# FONA-Data-Logger-Board.net
KiCad netlist of a schematic drawn in EAGLE
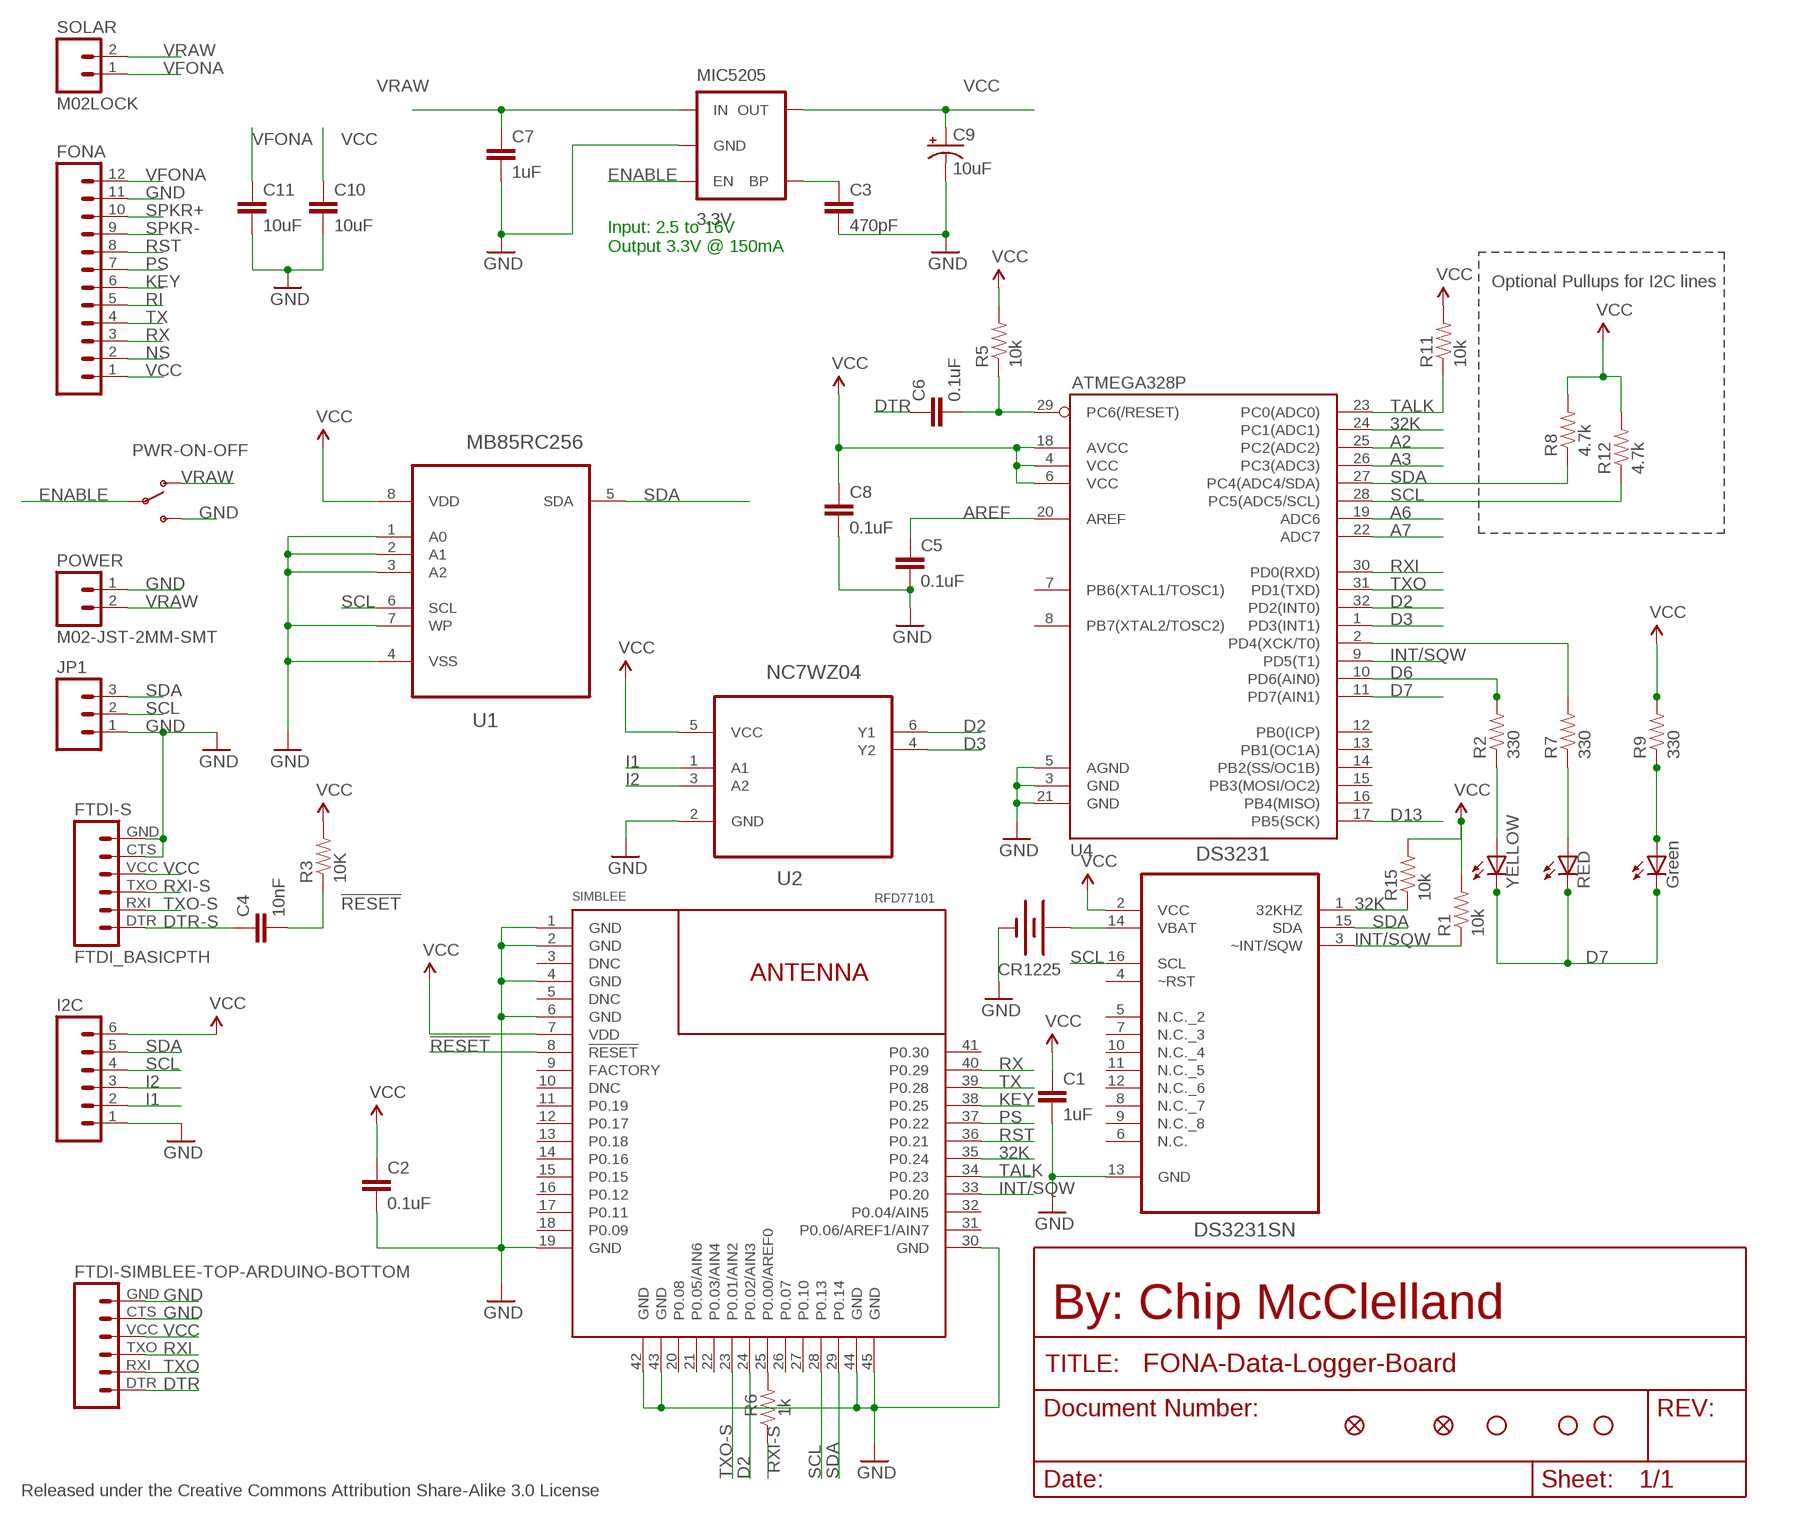
[diagram p0: schematic, sheet 1]

(export (version "E")
  (design (tool "Eeschema 10.0.6"))
  (components
    (comp (ref "ATMEGA328P")
      (value "U4")
      (footprint "eagle-import:TQFP32-08")
      (libsource (lib "eagle-import") (part "ATMEGA168"))
    )
    (comp (ref "C1")
      (value "1uF")
      (footprint "eagle-import:0805")
      (libsource (lib "eagle-import") (part "CAP0805"))
    )
    (comp (ref "C2")
      (value "0.1uF")
      (footprint "eagle-import:0805")
      (libsource (lib "eagle-import") (part "CAP0805"))
    )
    (comp (ref "C3")
      (value "470pF")
      (footprint "eagle-import:0805")
      (libsource (lib "eagle-import") (part "SparkFun-Passives_CAP0805"))
    )
    (comp (ref "C4")
      (value "10nF")
      (footprint "eagle-import:0805")
      (libsource (lib "eagle-import") (part "SparkFun-Passives_CAP0805"))
    )
    (comp (ref "C5")
      (value "0.1uF")
      (footprint "eagle-import:0805")
      (libsource (lib "eagle-import") (part "CAP0805"))
    )
    (comp (ref "C6")
      (value "0.1uF")
      (footprint "eagle-import:0805")
      (libsource (lib "eagle-import") (part "CAP0805"))
    )
    (comp (ref "C7")
      (value "1uF")
      (footprint "eagle-import:0805")
      (libsource (lib "eagle-import") (part "SparkFun-Passives_CAP0805"))
    )
    (comp (ref "C8")
      (value "0.1uF")
      (footprint "eagle-import:0805")
      (libsource (lib "eagle-import") (part "CAP0805"))
    )
    (comp (ref "C9")
      (value "10uF")
      (footprint "eagle-import:EIA3216")
      (libsource (lib "eagle-import") (part "CAP_POL1206"))
    )
    (comp (ref "C10")
      (value "10uF")
      (footprint "eagle-import:0805")
      (libsource (lib "eagle-import") (part "CAP0805"))
    )
    (comp (ref "C11")
      (value "10uF")
      (footprint "eagle-import:0805")
      (libsource (lib "eagle-import") (part "CAP0805"))
    )
    (comp (ref "CR1225")
      (value "BATTERY12MM")
      (footprint "eagle-import:BATTCON_12MM")
      (libsource (lib "eagle-import") (part "BATTERY12MM"))
    )
    (comp (ref "DS3231")
      (value "DS3231SN")
      (footprint "eagle-import:SOIC127P1032X265-16N")
      (fields (field (name "MPN") "DS3231SN#"))
      (libsource (lib "eagle-import") (part "DS3231SN"))
    )
    (comp (ref "FID1")
      (value "FIDUCIALUFIDUCIAL")
      (footprint "eagle-import:MICRO-FIDUCIAL")
      (libsource (lib "eagle-import") (part "FIDUCIALUFIDUCIAL"))
    )
    (comp (ref "FID2")
      (value "FIDUCIALUFIDUCIAL")
      (footprint "eagle-import:MICRO-FIDUCIAL")
      (libsource (lib "eagle-import") (part "FIDUCIALUFIDUCIAL"))
    )
    (comp (ref "FONA")
      (value "M12PTH")
      (footprint "eagle-import:1X12")
      (libsource (lib "eagle-import") (part "M12PTH"))
    )
    (comp (ref "FTDI-S")
      (value "FTDI_BASICPTH")
      (footprint "eagle-import:FTDI_BASIC")
      (libsource (lib "eagle-import") (part "FTDI_BASICPTH"))
    )
    (comp (ref "FTDI-SIMBLEE-TOP-ARDUINO-BOTTOM")
      (value "FTDI Basic")
      (footprint "eagle-import:FTDI_BASIC")
      (libsource (lib "eagle-import") (part "FTDI_BASICPTH"))
    )
    (comp (ref "G")
      (value "Green")
      (footprint "eagle-import:CHIPLED_0805")
      (libsource (lib "eagle-import") (part "LEDCHIPLED_0805"))
    )
    (comp (ref "I2C")
      (value "M06LOCK")
      (footprint "eagle-import:1X06_LOCK")
      (libsource (lib "eagle-import") (part "M06LOCK"))
    )
    (comp (ref "JP1")
      (value "M03LOCK")
      (footprint "eagle-import:1X03_LOCK")
      (libsource (lib "eagle-import") (part "M03LOCK"))
    )
    (comp (ref "JP3")
      (value "STAND-OFF")
      (footprint "eagle-import:STAND-OFF")
      (libsource (lib "eagle-import") (part "STAND-OFF"))
    )
    (comp (ref "JP4")
      (value "STAND-OFF")
      (footprint "eagle-import:STAND-OFF")
      (libsource (lib "eagle-import") (part "STAND-OFF"))
    )
    (comp (ref "JP6")
      (value "STAND-OFF")
      (footprint "eagle-import:STAND-OFF")
      (libsource (lib "eagle-import") (part "STAND-OFF"))
    )
    (comp (ref "MB85RC256")
      (value "U1")
      (footprint "eagle-import:SOIC127P600X175-8N")
      (fields (field (name "MPN") "MB85RC128PNF-G-JNE1"))
      (libsource (lib "eagle-import") (part "MB85RC128PNF-G-JNE1"))
    )
    (comp (ref "MIC5205")
      (value "3.3V")
      (footprint "eagle-import:SOT23-5")
      (libsource (lib "eagle-import") (part "MIC52053.3V"))
    )
    (comp (ref "NC7WZ04")
      (value "U2")
      (footprint "eagle-import:SOT65P210X110-6N")
      (fields (field (name "MPN") "NC7WZ04P6X"))
      (libsource (lib "eagle-import") (part "NC7WZ04P6X"))
    )
    (comp (ref "POWER")
      (value "M02-JST-2MM-SMT")
      (footprint "eagle-import:JST-2-SMD")
      (libsource (lib "eagle-import") (part "M02-JST-2MM-SMT"))
    )
    (comp (ref "PWR-ON-OFF")
      (value "SWITCH-SPDTPTH")
      (footprint "eagle-import:SWITCH-SPDT")
      (libsource (lib "eagle-import") (part "SWITCH-SPDTPTH"))
    )
    (comp (ref "R")
      (value "RED")
      (footprint "eagle-import:CHIPLED_0805")
      (libsource (lib "eagle-import") (part "LEDCHIPLED_0805"))
    )
    (comp (ref "R1")
      (value "10k")
      (footprint "eagle-import:0805")
      (libsource (lib "eagle-import") (part "RESISTOR0805-RES"))
    )
    (comp (ref "R2")
      (value "330")
      (footprint "eagle-import:0603-RES")
      (libsource (lib "eagle-import") (part "RESISTOR0603"))
    )
    (comp (ref "R3")
      (value "10K")
      (footprint "eagle-import:0805")
      (libsource (lib "eagle-import") (part "RESISTOR0805-RES"))
    )
    (comp (ref "R5")
      (value "10k")
      (footprint "eagle-import:0805")
      (libsource (lib "eagle-import") (part "RESISTOR0805-RES"))
    )
    (comp (ref "R6")
      (value "1k")
      (footprint "eagle-import:0805")
      (libsource (lib "eagle-import") (part "RESISTOR0805-RES"))
    )
    (comp (ref "R7")
      (value "330")
      (footprint "eagle-import:0603-RES")
      (libsource (lib "eagle-import") (part "RESISTOR0603"))
    )
    (comp (ref "R8")
      (value "4.7k")
      (footprint "eagle-import:0805")
      (libsource (lib "eagle-import") (part "SparkFun-Resistors_RESISTOR0805-RES"))
    )
    (comp (ref "R9")
      (value "330")
      (footprint "eagle-import:0603-RES")
      (libsource (lib "eagle-import") (part "RESISTOR0603"))
    )
    (comp (ref "R11")
      (value "10k")
      (footprint "eagle-import:0805")
      (libsource (lib "eagle-import") (part "RESISTOR0805-RES"))
    )
    (comp (ref "R12")
      (value "4.7k")
      (footprint "eagle-import:0805")
      (libsource (lib "eagle-import") (part "SparkFun-Resistors_RESISTOR0805-RES"))
    )
    (comp (ref "R15")
      (value "10k")
      (footprint "eagle-import:0805")
      (libsource (lib "eagle-import") (part "RESISTOR0805-RES"))
    )
    (comp (ref "SIMBLEE")
      (value "RFD77101")
      (footprint "eagle-import:RFD77101")
      (libsource (lib "eagle-import") (part "RFD77101"))
    )
    (comp (ref "SOLAR")
      (value "M02LOCK")
      (footprint "eagle-import:1X02_LOCK")
      (libsource (lib "eagle-import") (part "M02LOCK"))
    )
    (comp (ref "Y")
      (value "YELLOW")
      (footprint "eagle-import:CHIPLED_0805")
      (libsource (lib "eagle-import") (part "LEDCHIPLED_0805"))
    )
  )
  (nets
    (net (code "1") (name "/32K") (class "Default")
      (node (ref "ATMEGA328P") (pin "24") (pinfunction "PC1(ADC1)_24") (pintype "bidirectional"))
      (node (ref "DS3231") (pin "1") (pinfunction "32KHZ_1") (pintype "output"))
      (node (ref "R15") (pin "1") (pinfunction "1_1") (pintype "passive"))
      (node (ref "SIMBLEE") (pin "35") (pinfunction "P0.24_35") (pintype "bidirectional"))
    )
    (net (code "2") (name "/A2") (class "Default")
      (node (ref "ATMEGA328P") (pin "25") (pinfunction "PC2(ADC2)_25") (pintype "bidirectional"))
    )
    (net (code "3") (name "/A3") (class "Default")
      (node (ref "ATMEGA328P") (pin "26") (pinfunction "PC3(ADC3)_26") (pintype "bidirectional"))
    )
    (net (code "4") (name "/A6") (class "Default")
      (node (ref "ATMEGA328P") (pin "19") (pinfunction "ADC6_19") (pintype "bidirectional"))
    )
    (net (code "5") (name "/A7") (class "Default")
      (node (ref "ATMEGA328P") (pin "22") (pinfunction "ADC7_22") (pintype "bidirectional"))
    )
    (net (code "6") (name "/AREF") (class "Default")
      (node (ref "ATMEGA328P") (pin "20") (pinfunction "AREF_20") (pintype "bidirectional"))
      (node (ref "C5") (pin "1") (pinfunction "1_1") (pintype "passive"))
    )
    (net (code "7") (name "/D2") (class "Default")
      (node (ref "ATMEGA328P") (pin "32") (pinfunction "PD2(INT0)_32") (pintype "bidirectional"))
      (node (ref "NC7WZ04") (pin "6") (pinfunction "Y1_6") (pintype "output"))
      (node (ref "SIMBLEE") (pin "24") (pinfunction "P0.02/AIN3_24") (pintype "bidirectional"))
    )
    (net (code "8") (name "/D3") (class "Default")
      (node (ref "ATMEGA328P") (pin "1") (pinfunction "PD3(INT1)_1") (pintype "bidirectional"))
      (node (ref "NC7WZ04") (pin "4") (pinfunction "Y2_4") (pintype "output"))
    )
    (net (code "9") (name "/D6") (class "Default")
      (node (ref "ATMEGA328P") (pin "10") (pinfunction "PD6(AIN0)_10") (pintype "bidirectional"))
      (node (ref "R2") (pin "2") (pinfunction "2_2") (pintype "passive"))
    )
    (net (code "10") (name "/D7") (class "Default")
      (node (ref "ATMEGA328P") (pin "11") (pinfunction "PD7(AIN1)_11") (pintype "bidirectional"))
      (node (ref "G") (pin "C") (pinfunction "C_C") (pintype "passive"))
      (node (ref "R") (pin "C") (pinfunction "C_C") (pintype "passive"))
      (node (ref "Y") (pin "C") (pinfunction "C_C") (pintype "passive"))
    )
    (net (code "11") (name "/D13") (class "Default")
      (node (ref "ATMEGA328P") (pin "17") (pinfunction "PB5(SCK)_17") (pintype "bidirectional"))
    )
    (net (code "12") (name "/DTR") (class "Default")
      (node (ref "C6") (pin "1") (pinfunction "1_1") (pintype "passive"))
      (node (ref "FTDI-SIMBLEE-TOP-ARDUINO-BOTTOM") (pin "DTR") (pinfunction "1_DTR") (pintype "passive"))
    )
    (net (code "13") (name "/DTR-S") (class "Default")
      (node (ref "C4") (pin "1") (pinfunction "1_1") (pintype "passive"))
      (node (ref "FTDI-S") (pin "DTR") (pinfunction "1_DTR") (pintype "passive"))
    )
    (net (code "14") (name "/ENABLE") (class "Default")
      (node (ref "MIC5205") (pin "3") (pinfunction "EN_3") (pintype "input"))
      (node (ref "PWR-ON-OFF") (pin "2") (pinfunction "P_2") (pintype "passive"))
    )
    (net (code "15") (name "/I1") (class "Default")
      (node (ref "I2C") (pin "2") (pinfunction "2_2") (pintype "passive"))
      (node (ref "NC7WZ04") (pin "1") (pinfunction "A1_1") (pintype "input"))
    )
    (net (code "16") (name "/I2") (class "Default")
      (node (ref "I2C") (pin "3") (pinfunction "3_3") (pintype "passive"))
      (node (ref "NC7WZ04") (pin "3") (pinfunction "A2_3") (pintype "input"))
    )
    (net (code "17") (name "/INT{slash}SQW") (class "Default")
      (node (ref "ATMEGA328P") (pin "9") (pinfunction "PD5(T1)_9") (pintype "bidirectional"))
      (node (ref "DS3231") (pin "3") (pinfunction "~{INT/SQW}_3") (pintype "output"))
      (node (ref "R1") (pin "1") (pinfunction "1_1") (pintype "passive"))
      (node (ref "SIMBLEE") (pin "33") (pinfunction "P0.20_33") (pintype "bidirectional"))
    )
    (net (code "18") (name "/KEY") (class "Default")
      (node (ref "FONA") (pin "6") (pinfunction "6_6") (pintype "passive"))
      (node (ref "SIMBLEE") (pin "38") (pinfunction "P0.25_38") (pintype "bidirectional"))
    )
    (net (code "19") (name "/NS") (class "Default")
      (node (ref "FONA") (pin "2") (pinfunction "2_2") (pintype "passive"))
    )
    (net (code "20") (name "/PS") (class "Default")
      (node (ref "FONA") (pin "7") (pinfunction "7_7") (pintype "passive"))
      (node (ref "SIMBLEE") (pin "37") (pinfunction "P0.22_37") (pintype "bidirectional"))
    )
    (net (code "21") (name "/RI") (class "Default")
      (node (ref "FONA") (pin "5") (pinfunction "5_5") (pintype "passive"))
    )
    (net (code "22") (name "/RST") (class "Default")
      (node (ref "FONA") (pin "8") (pinfunction "8_8") (pintype "passive"))
      (node (ref "SIMBLEE") (pin "36") (pinfunction "P0.21_36") (pintype "bidirectional"))
    )
    (net (code "23") (name "/RX") (class "Default")
      (node (ref "FONA") (pin "3") (pinfunction "3_3") (pintype "passive"))
      (node (ref "SIMBLEE") (pin "40") (pinfunction "P0.29_40") (pintype "bidirectional"))
    )
    (net (code "24") (name "/RXI") (class "Default")
      (node (ref "ATMEGA328P") (pin "30") (pinfunction "PD0(RXD)_30") (pintype "bidirectional"))
      (node (ref "FTDI-SIMBLEE-TOP-ARDUINO-BOTTOM") (pin "TXO") (pinfunction "3_TXO") (pintype "passive"))
    )
    (net (code "25") (name "/RXI-S") (class "Default")
      (node (ref "FTDI-S") (pin "TXO") (pinfunction "3_TXO") (pintype "passive"))
      (node (ref "R6") (pin "1") (pinfunction "1_1") (pintype "passive"))
    )
    (net (code "26") (name "/SCL") (class "Default")
      (node (ref "ATMEGA328P") (pin "28") (pinfunction "PC5(ADC5/SCL)_28") (pintype "bidirectional"))
      (node (ref "DS3231") (pin "16") (pinfunction "SCL_16") (pintype "input"))
      (node (ref "I2C") (pin "4") (pinfunction "4_4") (pintype "passive"))
      (node (ref "JP1") (pin "2") (pinfunction "2_2") (pintype "passive"))
      (node (ref "MB85RC256") (pin "6") (pinfunction "SCL_6") (pintype "input"))
      (node (ref "R12") (pin "1") (pinfunction "1_1") (pintype "passive"))
      (node (ref "SIMBLEE") (pin "28") (pinfunction "P0.13_28") (pintype "bidirectional"))
    )
    (net (code "27") (name "/SDA") (class "Default")
      (node (ref "ATMEGA328P") (pin "27") (pinfunction "PC4(ADC4/SDA)_27") (pintype "bidirectional"))
      (node (ref "DS3231") (pin "15") (pinfunction "SDA_15") (pintype "bidirectional"))
      (node (ref "I2C") (pin "5") (pinfunction "5_5") (pintype "passive"))
      (node (ref "JP1") (pin "3") (pinfunction "3_3") (pintype "passive"))
      (node (ref "MB85RC256") (pin "5") (pinfunction "SDA_5") (pintype "bidirectional"))
      (node (ref "R8") (pin "1") (pinfunction "1_1") (pintype "passive"))
      (node (ref "SIMBLEE") (pin "29") (pinfunction "P0.14_29") (pintype "bidirectional"))
    )
    (net (code "28") (name "/SPKR+") (class "Default")
      (node (ref "FONA") (pin "10") (pinfunction "10_10") (pintype "passive"))
    )
    (net (code "29") (name "/SPKR-") (class "Default")
      (node (ref "FONA") (pin "9") (pinfunction "9_9") (pintype "passive"))
    )
    (net (code "30") (name "/TALK") (class "Default")
      (node (ref "ATMEGA328P") (pin "23") (pinfunction "PC0(ADC0)_23") (pintype "bidirectional"))
      (node (ref "R11") (pin "1") (pinfunction "1_1") (pintype "passive"))
      (node (ref "SIMBLEE") (pin "34") (pinfunction "P0.23_34") (pintype "bidirectional"))
    )
    (net (code "31") (name "/TX") (class "Default")
      (node (ref "FONA") (pin "4") (pinfunction "4_4") (pintype "passive"))
      (node (ref "SIMBLEE") (pin "39") (pinfunction "P0.28_39") (pintype "bidirectional"))
    )
    (net (code "32") (name "/TXO") (class "Default")
      (node (ref "ATMEGA328P") (pin "31") (pinfunction "PD1(TXD)_31") (pintype "bidirectional"))
      (node (ref "FTDI-SIMBLEE-TOP-ARDUINO-BOTTOM") (pin "RXI") (pinfunction "2_RXI") (pintype "passive"))
    )
    (net (code "33") (name "/TXO-S") (class "Default")
      (node (ref "FTDI-S") (pin "RXI") (pinfunction "2_RXI") (pintype "passive"))
      (node (ref "SIMBLEE") (pin "23") (pinfunction "P0.01/AIN2_23") (pintype "bidirectional"))
    )
    (net (code "34") (name "/VFONA") (class "Default")
      (node (ref "C11") (pin "1") (pinfunction "1_1") (pintype "passive"))
      (node (ref "FONA") (pin "12") (pinfunction "12_12") (pintype "passive"))
      (node (ref "SOLAR") (pin "1") (pinfunction "1_1") (pintype "passive"))
    )
    (net (code "35") (name "/VRAW") (class "Default")
      (node (ref "C7") (pin "1") (pinfunction "1_1") (pintype "passive"))
      (node (ref "MIC5205") (pin "1") (pinfunction "IN_1") (pintype "input"))
      (node (ref "POWER") (pin "2") (pinfunction "1_2") (pintype "passive"))
      (node (ref "PWR-ON-OFF") (pin "1") (pinfunction "O_1") (pintype "passive"))
      (node (ref "SOLAR") (pin "2") (pinfunction "2_2") (pintype "passive"))
    )
    (net (code "36") (name "/~{RESET}") (class "Default")
      (node (ref "C4") (pin "2") (pinfunction "2_2") (pintype "passive"))
      (node (ref "R3") (pin "1") (pinfunction "1_1") (pintype "passive"))
      (node (ref "SIMBLEE") (pin "8") (pinfunction "~{RESET}_8") (pintype "input"))
    )
    (net (code "37") (name "GND") (class "Default")
      (node (ref "ATMEGA328P") (pin "21") (pinfunction "GND_21") (pintype "bidirectional"))
      (node (ref "ATMEGA328P") (pin "3") (pinfunction "GND_3") (pintype "bidirectional"))
      (node (ref "ATMEGA328P") (pin "5") (pinfunction "AGND_5") (pintype "bidirectional"))
      (node (ref "C1") (pin "2") (pinfunction "2_2") (pintype "passive"))
      (node (ref "C10") (pin "2") (pinfunction "2_2") (pintype "passive"))
      (node (ref "C11") (pin "2") (pinfunction "2_2") (pintype "passive"))
      (node (ref "C2") (pin "2") (pinfunction "2_2") (pintype "passive"))
      (node (ref "C3") (pin "2") (pinfunction "2_2") (pintype "passive"))
      (node (ref "C5") (pin "2") (pinfunction "2_2") (pintype "passive"))
      (node (ref "C7") (pin "2") (pinfunction "2_2") (pintype "passive"))
      (node (ref "C8") (pin "2") (pinfunction "2_2") (pintype "passive"))
      (node (ref "C9") (pin "C") (pinfunction "-_C") (pintype "passive"))
      (node (ref "CR1225") (pin "GND") (pinfunction "-_GND") (pintype "power_in"))
      (node (ref "DS3231") (pin "13") (pinfunction "GND_13") (pintype "passive"))
      (node (ref "FONA") (pin "11") (pinfunction "11_11") (pintype "passive"))
      (node (ref "FTDI-S") (pin "CTS") (pinfunction "5_CTS") (pintype "passive"))
      (node (ref "FTDI-S") (pin "GND") (pinfunction "6_GND") (pintype "passive"))
      (node (ref "FTDI-SIMBLEE-TOP-ARDUINO-BOTTOM") (pin "CTS") (pinfunction "5_CTS") (pintype "passive"))
      (node (ref "FTDI-SIMBLEE-TOP-ARDUINO-BOTTOM") (pin "GND") (pinfunction "6_GND") (pintype "passive"))
      (node (ref "I2C") (pin "1") (pinfunction "1_1") (pintype "passive"))
      (node (ref "JP1") (pin "1") (pinfunction "1_1") (pintype "passive"))
      (node (ref "MB85RC256") (pin "1") (pinfunction "A0_1") (pintype "input"))
      (node (ref "MB85RC256") (pin "2") (pinfunction "A1_2") (pintype "input"))
      (node (ref "MB85RC256") (pin "3") (pinfunction "A2_3") (pintype "input"))
      (node (ref "MB85RC256") (pin "4") (pinfunction "VSS_4") (pintype "passive"))
      (node (ref "MB85RC256") (pin "7") (pinfunction "WP_7") (pintype "input"))
      (node (ref "MIC5205") (pin "2") (pinfunction "GND_2") (pintype "input"))
      (node (ref "NC7WZ04") (pin "2") (pinfunction "GND_2") (pintype "passive"))
      (node (ref "POWER") (pin "1") (pinfunction "2_1") (pintype "passive"))
      (node (ref "PWR-ON-OFF") (pin "3") (pinfunction "S_3") (pintype "passive"))
      (node (ref "SIMBLEE") (pin "1") (pinfunction "GND_1") (pintype "power_in"))
      (node (ref "SIMBLEE") (pin "19") (pinfunction "GND_19") (pintype "power_in"))
      (node (ref "SIMBLEE") (pin "2") (pinfunction "GND_2") (pintype "power_in"))
      (node (ref "SIMBLEE") (pin "30") (pinfunction "GND_30") (pintype "power_in"))
      (node (ref "SIMBLEE") (pin "4") (pinfunction "GND_4") (pintype "power_in"))
      (node (ref "SIMBLEE") (pin "42") (pinfunction "GND_42") (pintype "power_in"))
      (node (ref "SIMBLEE") (pin "43") (pinfunction "GND_43") (pintype "power_in"))
      (node (ref "SIMBLEE") (pin "44") (pinfunction "GND_44") (pintype "power_in"))
      (node (ref "SIMBLEE") (pin "45") (pinfunction "GND_45") (pintype "power_in"))
      (node (ref "SIMBLEE") (pin "6") (pinfunction "GND_6") (pintype "power_in"))
    )
    (net (code "38") (name "Net-(ATMEGA328P-PC6({slash}RESET))") (class "Default")
      (node (ref "ATMEGA328P") (pin "29") (pinfunction "PC6(/RESET)_29") (pintype "bidirectional"))
      (node (ref "C6") (pin "2") (pinfunction "2_2") (pintype "passive"))
      (node (ref "R5") (pin "1") (pinfunction "1_1") (pintype "passive"))
    )
    (net (code "39") (name "Net-(ATMEGA328P-PD4(XCK{slash}T0))") (class "Default")
      (node (ref "ATMEGA328P") (pin "2") (pinfunction "PD4(XCK/T0)_2") (pintype "bidirectional"))
      (node (ref "R7") (pin "2") (pinfunction "2_2") (pintype "passive"))
    )
    (net (code "40") (name "Net-(CR1225-+)") (class "Default")
      (node (ref "CR1225") (pin "PWR@1") (pinfunction "+_PWR@1") (pintype "power_in"))
      (node (ref "DS3231") (pin "14") (pinfunction "VBAT_14") (pintype "power_in"))
    )
    (net (code "41") (name "Net-(G-PadA)") (class "Default")
      (node (ref "G") (pin "A") (pinfunction "A_A") (pintype "passive"))
      (node (ref "R9") (pin "1") (pinfunction "1_1") (pintype "passive"))
    )
    (net (code "42") (name "Net-(MIC5205-BP)") (class "Default")
      (node (ref "C3") (pin "1") (pinfunction "1_1") (pintype "passive"))
      (node (ref "MIC5205") (pin "4") (pinfunction "BP_4") (pintype "input"))
    )
    (net (code "43") (name "Net-(R-PadA)") (class "Default")
      (node (ref "R") (pin "A") (pinfunction "A_A") (pintype "passive"))
      (node (ref "R7") (pin "1") (pinfunction "1_1") (pintype "passive"))
    )
    (net (code "44") (name "Net-(R2-Pad1)") (class "Default")
      (node (ref "R2") (pin "1") (pinfunction "1_1") (pintype "passive"))
      (node (ref "Y") (pin "A") (pinfunction "A_A") (pintype "passive"))
    )
    (net (code "45") (name "Net-(SIMBLEE-P0.00{slash}AREF0)") (class "Default")
      (node (ref "R6") (pin "2") (pinfunction "2_2") (pintype "passive"))
      (node (ref "SIMBLEE") (pin "25") (pinfunction "P0.00/AREF0_25") (pintype "bidirectional"))
    )
    (net (code "46") (name "VCC") (class "Default")
      (node (ref "ATMEGA328P") (pin "18") (pinfunction "AVCC_18") (pintype "bidirectional"))
      (node (ref "ATMEGA328P") (pin "4") (pinfunction "VCC_4") (pintype "bidirectional"))
      (node (ref "ATMEGA328P") (pin "6") (pinfunction "VCC_6") (pintype "bidirectional"))
      (node (ref "C1") (pin "1") (pinfunction "1_1") (pintype "passive"))
      (node (ref "C10") (pin "1") (pinfunction "1_1") (pintype "passive"))
      (node (ref "C2") (pin "1") (pinfunction "1_1") (pintype "passive"))
      (node (ref "C8") (pin "1") (pinfunction "1_1") (pintype "passive"))
      (node (ref "C9") (pin "A") (pinfunction "+_A") (pintype "passive"))
      (node (ref "DS3231") (pin "2") (pinfunction "VCC_2") (pintype "power_in"))
      (node (ref "FONA") (pin "1") (pinfunction "1_1") (pintype "passive"))
      (node (ref "FTDI-S") (pin "VCC") (pinfunction "4_VCC") (pintype "passive"))
      (node (ref "FTDI-SIMBLEE-TOP-ARDUINO-BOTTOM") (pin "VCC") (pinfunction "4_VCC") (pintype "passive"))
      (node (ref "I2C") (pin "6") (pinfunction "6_6") (pintype "passive"))
      (node (ref "MB85RC256") (pin "8") (pinfunction "VDD_8") (pintype "power_in"))
      (node (ref "MIC5205") (pin "5") (pinfunction "OUT_5") (pintype "passive"))
      (node (ref "NC7WZ04") (pin "5") (pinfunction "VCC_5") (pintype "power_in"))
      (node (ref "R1") (pin "2") (pinfunction "2_2") (pintype "passive"))
      (node (ref "R11") (pin "2") (pinfunction "2_2") (pintype "passive"))
      (node (ref "R12") (pin "2") (pinfunction "2_2") (pintype "passive"))
      (node (ref "R15") (pin "2") (pinfunction "2_2") (pintype "passive"))
      (node (ref "R3") (pin "2") (pinfunction "2_2") (pintype "passive"))
      (node (ref "R5") (pin "2") (pinfunction "2_2") (pintype "passive"))
      (node (ref "R8") (pin "2") (pinfunction "2_2") (pintype "passive"))
      (node (ref "R9") (pin "2") (pinfunction "2_2") (pintype "passive"))
      (node (ref "SIMBLEE") (pin "7") (pinfunction "VDD_7") (pintype "power_in"))
    )
    (net (code "47") (name "unconnected-(ATMEGA328P-PB0(ICP)-Pad12)") (class "Default")
      (node (ref "ATMEGA328P") (pin "12") (pinfunction "PB0(ICP)_12") (pintype "bidirectional"))
    )
    (net (code "48") (name "unconnected-(ATMEGA328P-PB1(OC1A)-Pad13)") (class "Default")
      (node (ref "ATMEGA328P") (pin "13") (pinfunction "PB1(OC1A)_13") (pintype "bidirectional"))
    )
    (net (code "49") (name "unconnected-(ATMEGA328P-PB2(SS{slash}OC1B)-Pad14)") (class "Default")
      (node (ref "ATMEGA328P") (pin "14") (pinfunction "PB2(SS/OC1B)_14") (pintype "bidirectional"))
    )
    (net (code "50") (name "unconnected-(ATMEGA328P-PB3(MOSI{slash}OC2)-Pad15)") (class "Default")
      (node (ref "ATMEGA328P") (pin "15") (pinfunction "PB3(MOSI/OC2)_15") (pintype "bidirectional"))
    )
    (net (code "51") (name "unconnected-(ATMEGA328P-PB4(MISO)-Pad16)") (class "Default")
      (node (ref "ATMEGA328P") (pin "16") (pinfunction "PB4(MISO)_16") (pintype "bidirectional"))
    )
    (net (code "52") (name "unconnected-(ATMEGA328P-PB6(XTAL1{slash}TOSC1)-Pad7)") (class "Default")
      (node (ref "ATMEGA328P") (pin "7") (pinfunction "PB6(XTAL1/TOSC1)_7") (pintype "bidirectional"))
    )
    (net (code "53") (name "unconnected-(ATMEGA328P-PB7(XTAL2{slash}TOSC2)-Pad8)") (class "Default")
      (node (ref "ATMEGA328P") (pin "8") (pinfunction "PB7(XTAL2/TOSC2)_8") (pintype "bidirectional"))
    )
    (net (code "54") (name "unconnected-(DS3231-N.C.-Pad6)") (class "Default")
      (node (ref "DS3231") (pin "6") (pinfunction "N.C._6") (pintype "no_connect"))
    )
    (net (code "55") (name "unconnected-(DS3231-N.C._2-Pad5)") (class "Default")
      (node (ref "DS3231") (pin "5") (pinfunction "N.C._2_5") (pintype "no_connect"))
    )
    (net (code "56") (name "unconnected-(DS3231-N.C._3-Pad7)") (class "Default")
      (node (ref "DS3231") (pin "7") (pinfunction "N.C._3_7") (pintype "no_connect"))
    )
    (net (code "57") (name "unconnected-(DS3231-N.C._4-Pad10)") (class "Default")
      (node (ref "DS3231") (pin "10") (pinfunction "N.C._4_10") (pintype "no_connect"))
    )
    (net (code "58") (name "unconnected-(DS3231-N.C._5-Pad11)") (class "Default")
      (node (ref "DS3231") (pin "11") (pinfunction "N.C._5_11") (pintype "no_connect"))
    )
    (net (code "59") (name "unconnected-(DS3231-N.C._6-Pad12)") (class "Default")
      (node (ref "DS3231") (pin "12") (pinfunction "N.C._6_12") (pintype "no_connect"))
    )
    (net (code "60") (name "unconnected-(DS3231-N.C._7-Pad8)") (class "Default")
      (node (ref "DS3231") (pin "8") (pinfunction "N.C._7_8") (pintype "no_connect"))
    )
    (net (code "61") (name "unconnected-(DS3231-N.C._8-Pad9)") (class "Default")
      (node (ref "DS3231") (pin "9") (pinfunction "N.C._8_9") (pintype "no_connect"))
    )
    (net (code "62") (name "unconnected-(DS3231-~{RST}-Pad4)") (class "Default")
      (node (ref "DS3231") (pin "4") (pinfunction "~{RST}_4") (pintype "bidirectional"))
    )
    (net (code "63") (name "unconnected-(SIMBLEE-DNC-Pad3)") (class "Default")
      (node (ref "SIMBLEE") (pin "3") (pinfunction "DNC_3") (pintype "no_connect"))
    )
    (net (code "64") (name "unconnected-(SIMBLEE-DNC-Pad5)") (class "Default")
      (node (ref "SIMBLEE") (pin "5") (pinfunction "DNC_5") (pintype "no_connect"))
    )
    (net (code "65") (name "unconnected-(SIMBLEE-DNC-Pad10)") (class "Default")
      (node (ref "SIMBLEE") (pin "10") (pinfunction "DNC_10") (pintype "no_connect"))
    )
    (net (code "66") (name "unconnected-(SIMBLEE-FACTORY-Pad9)") (class "Default")
      (node (ref "SIMBLEE") (pin "9") (pinfunction "FACTORY_9") (pintype "no_connect"))
    )
    (net (code "67") (name "unconnected-(SIMBLEE-P0.03{slash}AIN4-Pad22)") (class "Default")
      (node (ref "SIMBLEE") (pin "22") (pinfunction "P0.03/AIN4_22") (pintype "bidirectional"))
    )
    (net (code "68") (name "unconnected-(SIMBLEE-P0.04{slash}AIN5-Pad32)") (class "Default")
      (node (ref "SIMBLEE") (pin "32") (pinfunction "P0.04/AIN5_32") (pintype "bidirectional"))
    )
    (net (code "69") (name "unconnected-(SIMBLEE-P0.05{slash}AIN6-Pad21)") (class "Default")
      (node (ref "SIMBLEE") (pin "21") (pinfunction "P0.05/AIN6_21") (pintype "bidirectional"))
    )
    (net (code "70") (name "unconnected-(SIMBLEE-P0.06{slash}AREF1{slash}AIN7-Pad31)") (class "Default")
      (node (ref "SIMBLEE") (pin "31") (pinfunction "P0.06/AREF1/AIN7_31") (pintype "bidirectional"))
    )
    (net (code "71") (name "unconnected-(SIMBLEE-P0.07-Pad26)") (class "Default")
      (node (ref "SIMBLEE") (pin "26") (pinfunction "P0.07_26") (pintype "bidirectional"))
    )
    (net (code "72") (name "unconnected-(SIMBLEE-P0.08-Pad20)") (class "Default")
      (node (ref "SIMBLEE") (pin "20") (pinfunction "P0.08_20") (pintype "bidirectional"))
    )
    (net (code "73") (name "unconnected-(SIMBLEE-P0.09-Pad18)") (class "Default")
      (node (ref "SIMBLEE") (pin "18") (pinfunction "P0.09_18") (pintype "bidirectional"))
    )
    (net (code "74") (name "unconnected-(SIMBLEE-P0.10-Pad27)") (class "Default")
      (node (ref "SIMBLEE") (pin "27") (pinfunction "P0.10_27") (pintype "bidirectional"))
    )
    (net (code "75") (name "unconnected-(SIMBLEE-P0.11-Pad17)") (class "Default")
      (node (ref "SIMBLEE") (pin "17") (pinfunction "P0.11_17") (pintype "bidirectional"))
    )
    (net (code "76") (name "unconnected-(SIMBLEE-P0.12-Pad16)") (class "Default")
      (node (ref "SIMBLEE") (pin "16") (pinfunction "P0.12_16") (pintype "bidirectional"))
    )
    (net (code "77") (name "unconnected-(SIMBLEE-P0.15-Pad15)") (class "Default")
      (node (ref "SIMBLEE") (pin "15") (pinfunction "P0.15_15") (pintype "bidirectional"))
    )
    (net (code "78") (name "unconnected-(SIMBLEE-P0.16-Pad14)") (class "Default")
      (node (ref "SIMBLEE") (pin "14") (pinfunction "P0.16_14") (pintype "bidirectional"))
    )
    (net (code "79") (name "unconnected-(SIMBLEE-P0.17-Pad12)") (class "Default")
      (node (ref "SIMBLEE") (pin "12") (pinfunction "P0.17_12") (pintype "bidirectional"))
    )
    (net (code "80") (name "unconnected-(SIMBLEE-P0.18-Pad13)") (class "Default")
      (node (ref "SIMBLEE") (pin "13") (pinfunction "P0.18_13") (pintype "bidirectional"))
    )
    (net (code "81") (name "unconnected-(SIMBLEE-P0.19-Pad11)") (class "Default")
      (node (ref "SIMBLEE") (pin "11") (pinfunction "P0.19_11") (pintype "bidirectional"))
    )
    (net (code "82") (name "unconnected-(SIMBLEE-P0.30-Pad41)") (class "Default")
      (node (ref "SIMBLEE") (pin "41") (pinfunction "P0.30_41") (pintype "bidirectional"))
    )
  )
)
